# CurrMeas.net
KiCad netlist of a schematic drawn in EAGLE
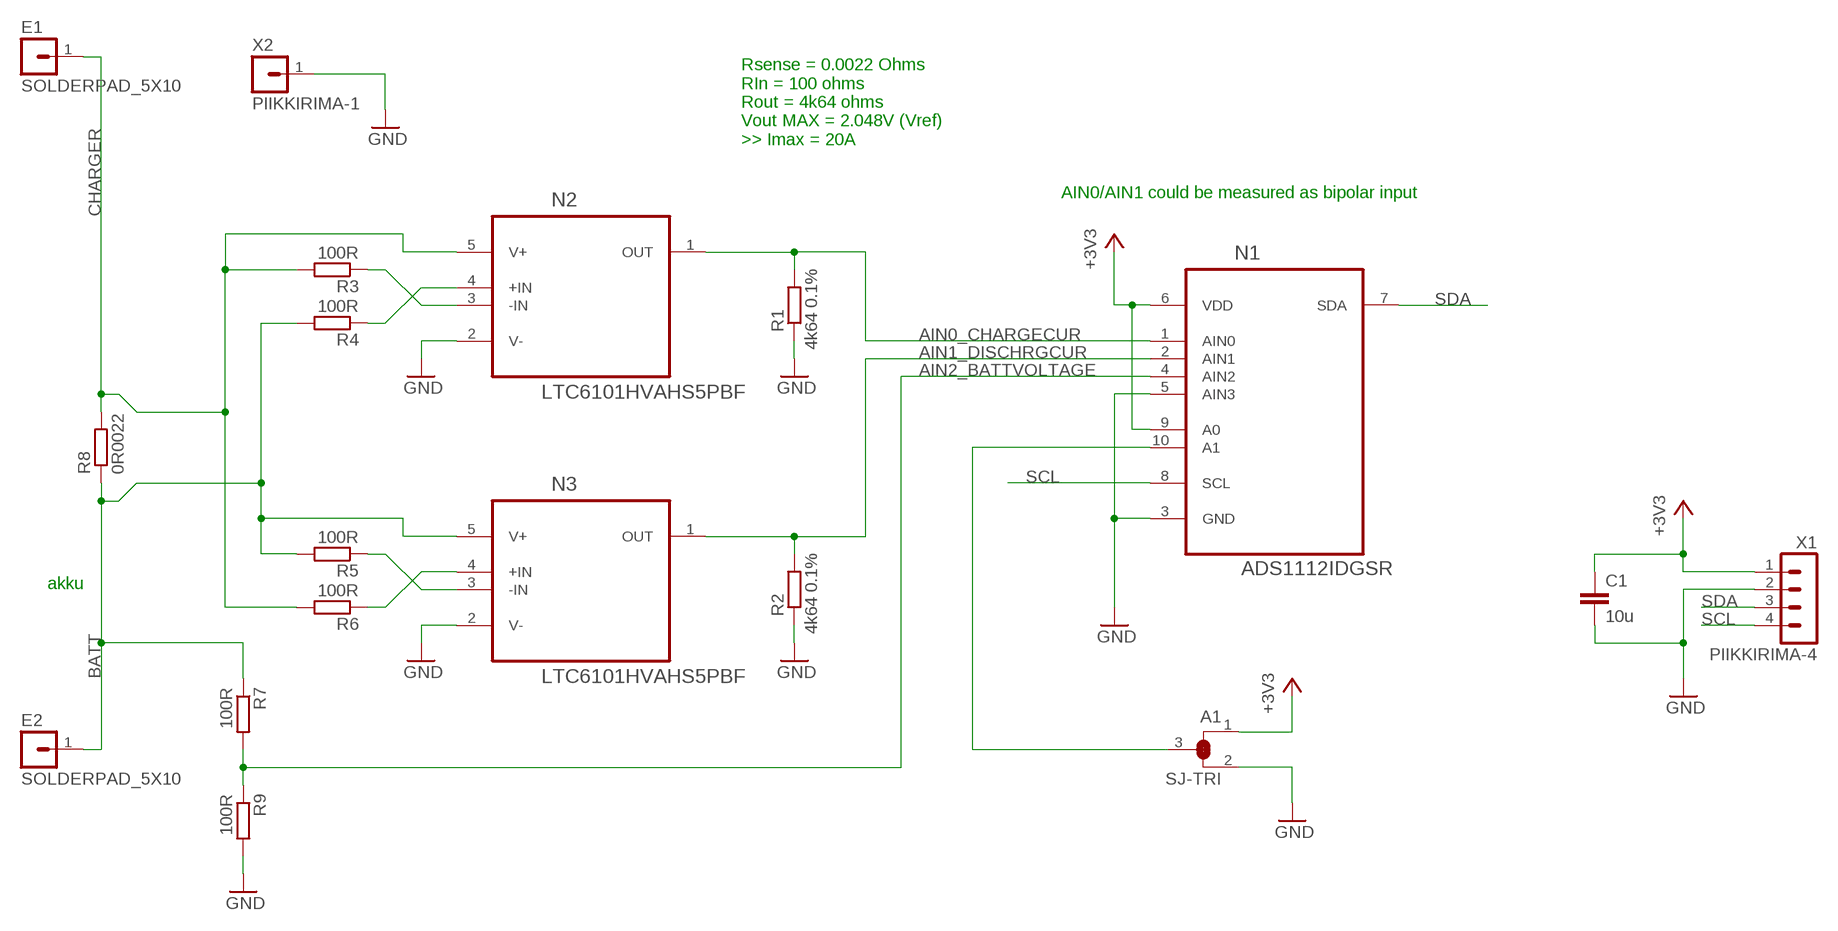
[diagram p0: schematic, sheet 1]

(export (version "E")
  (design (tool "Eeschema 10.0.6"))
  (components
    (comp (ref "A1")
      (value "SJ-TRI")
      (footprint "eagle-import:SJ-SMALL-TRI")
      (libsource (lib "eagle-import") (part "SJ-TRI"))
    )
    (comp (ref "C1")
      (value "10u")
      (footprint "eagle-import:C0805")
      (libsource (lib "eagle-import") (part "C-EUC0805"))
    )
    (comp (ref "E1")
      (value "SOLDERPAD_5X10")
      (footprint "eagle-import:SOLDERPAD_5X10")
      (libsource (lib "eagle-import") (part "SOLDERPAD_5X10"))
    )
    (comp (ref "E2")
      (value "SOLDERPAD_5X10")
      (footprint "eagle-import:SOLDERPAD_5X10")
      (libsource (lib "eagle-import") (part "SOLDERPAD_5X10"))
    )
    (comp (ref "N1")
      (value "ADS1112IDGSR")
      (footprint "eagle-import:SOP50P490X110-10N")
      (libsource (lib "eagle-import") (part "ADS1112IDGSR"))
    )
    (comp (ref "N2")
      (value "LTC6101HVAHS5PBF")
      (footprint "eagle-import:SOT95P280X100-5N")
      (fields (field (name "MPN") "LTC6101HVAHS5#PBF"))
      (libsource (lib "eagle-import") (part "LTC6101HVAHS5PBF"))
    )
    (comp (ref "N3")
      (value "LTC6101HVAHS5PBF")
      (footprint "eagle-import:SOT95P280X100-5N")
      (fields (field (name "MPN") "LTC6101HVAHS5#PBF"))
      (libsource (lib "eagle-import") (part "LTC6101HVAHS5PBF"))
    )
    (comp (ref "R1")
      (value "4k64 0.1%")
      (footprint "eagle-import:R0603")
      (libsource (lib "eagle-import") (part "R-EU_R0603"))
    )
    (comp (ref "R2")
      (value "4k64 0.1%")
      (footprint "eagle-import:R0603")
      (libsource (lib "eagle-import") (part "R-EU_R0603"))
    )
    (comp (ref "R3")
      (value "100R")
      (footprint "eagle-import:R0603")
      (libsource (lib "eagle-import") (part "R-EU_R0603"))
    )
    (comp (ref "R4")
      (value "100R")
      (footprint "eagle-import:R0603")
      (libsource (lib "eagle-import") (part "R-EU_R0603"))
    )
    (comp (ref "R5")
      (value "100R")
      (footprint "eagle-import:R0603")
      (libsource (lib "eagle-import") (part "R-EU_R0603"))
    )
    (comp (ref "R6")
      (value "100R")
      (footprint "eagle-import:R0603")
      (libsource (lib "eagle-import") (part "R-EU_R0603"))
    )
    (comp (ref "R7")
      (value "100R")
      (footprint "eagle-import:R0603")
      (libsource (lib "eagle-import") (part "R-EU_R0603"))
    )
    (comp (ref "R8")
      (value "0R0022")
      (footprint "eagle-import:R2512")
      (libsource (lib "eagle-import") (part "R-EU_R2512"))
    )
    (comp (ref "R9")
      (value "100R")
      (footprint "eagle-import:R0603")
      (libsource (lib "eagle-import") (part "R-EU_R0603"))
    )
    (comp (ref "X1")
      (value "PIIKKIRIMA-4")
      (footprint "eagle-import:PIIKKIRIMA-4")
      (libsource (lib "eagle-import") (part "PIIKKIRIMA-4"))
    )
    (comp (ref "X2")
      (value "PIIKKIRIMA-1")
      (footprint "eagle-import:PIIKKIRIMA-1")
      (libsource (lib "eagle-import") (part "PIIKKIRIMA-1"))
    )
  )
  (nets
    (net (code "1") (name "+3V3") (class "Default")
      (node (ref "A1") (pin "1") (pinfunction "1_1") (pintype "passive"))
      (node (ref "C1") (pin "1") (pinfunction "1_1") (pintype "passive"))
      (node (ref "N1") (pin "6") (pinfunction "VDD_6") (pintype "power_in"))
      (node (ref "N1") (pin "9") (pinfunction "A0_9") (pintype "input"))
      (node (ref "X1") (pin "1") (pinfunction "1_1") (pintype "passive"))
    )
    (net (code "2") (name "/AIN0_CHARGECUR") (class "Default")
      (node (ref "N1") (pin "1") (pinfunction "AIN0_1") (pintype "input"))
      (node (ref "N2") (pin "1") (pinfunction "OUT_1") (pintype "output"))
      (node (ref "R1") (pin "2") (pinfunction "2_2") (pintype "passive"))
    )
    (net (code "3") (name "/AIN1_DISCHRGCUR") (class "Default")
      (node (ref "N1") (pin "2") (pinfunction "AIN1_2") (pintype "input"))
      (node (ref "N3") (pin "1") (pinfunction "OUT_1") (pintype "output"))
      (node (ref "R2") (pin "2") (pinfunction "2_2") (pintype "passive"))
    )
    (net (code "4") (name "/AIN2_BATTVOLTAGE") (class "Default")
      (node (ref "N1") (pin "4") (pinfunction "AIN2_4") (pintype "input"))
      (node (ref "R7") (pin "2") (pinfunction "2_2") (pintype "passive"))
      (node (ref "R9") (pin "1") (pinfunction "1_1") (pintype "passive"))
    )
    (net (code "5") (name "/BATT") (class "Default")
      (node (ref "E2") (pin "1") (pinfunction "1_1") (pintype "passive"))
      (node (ref "N3") (pin "5") (pinfunction "V+_5") (pintype "power_in"))
      (node (ref "R4") (pin "2") (pinfunction "2_2") (pintype "passive"))
      (node (ref "R5") (pin "2") (pinfunction "2_2") (pintype "passive"))
      (node (ref "R7") (pin "1") (pinfunction "1_1") (pintype "passive"))
      (node (ref "R8") (pin "1") (pinfunction "1_1") (pintype "passive"))
    )
    (net (code "6") (name "/CHARGER") (class "Default")
      (node (ref "E1") (pin "1") (pinfunction "1_1") (pintype "passive"))
      (node (ref "N2") (pin "5") (pinfunction "V+_5") (pintype "power_in"))
      (node (ref "R3") (pin "2") (pinfunction "2_2") (pintype "passive"))
      (node (ref "R6") (pin "2") (pinfunction "2_2") (pintype "passive"))
      (node (ref "R8") (pin "2") (pinfunction "2_2") (pintype "passive"))
    )
    (net (code "7") (name "/SCL") (class "Default")
      (node (ref "N1") (pin "8") (pinfunction "SCL_8") (pintype "input"))
      (node (ref "X1") (pin "4") (pinfunction "4_4") (pintype "passive"))
    )
    (net (code "8") (name "/SDA") (class "Default")
      (node (ref "N1") (pin "7") (pinfunction "SDA_7") (pintype "bidirectional"))
      (node (ref "X1") (pin "3") (pinfunction "3_3") (pintype "passive"))
    )
    (net (code "9") (name "GND") (class "Default")
      (node (ref "A1") (pin "2") (pinfunction "2_2") (pintype "passive"))
      (node (ref "C1") (pin "2") (pinfunction "2_2") (pintype "passive"))
      (node (ref "N1") (pin "3") (pinfunction "GND_3") (pintype "passive"))
      (node (ref "N1") (pin "5") (pinfunction "AIN3_5") (pintype "input"))
      (node (ref "N2") (pin "2") (pinfunction "V-_2") (pintype "power_in"))
      (node (ref "N3") (pin "2") (pinfunction "V-_2") (pintype "power_in"))
      (node (ref "R1") (pin "1") (pinfunction "1_1") (pintype "passive"))
      (node (ref "R2") (pin "1") (pinfunction "1_1") (pintype "passive"))
      (node (ref "R9") (pin "2") (pinfunction "2_2") (pintype "passive"))
      (node (ref "X1") (pin "2") (pinfunction "2_2") (pintype "passive"))
      (node (ref "X2") (pin "1") (pinfunction "1_1") (pintype "passive"))
    )
    (net (code "10") (name "Net-(N1-A1)") (class "Default")
      (node (ref "A1") (pin "3") (pinfunction "3_3") (pintype "passive"))
      (node (ref "N1") (pin "10") (pinfunction "A1_10") (pintype "input"))
    )
    (net (code "11") (name "Net-(N2-+IN)") (class "Default")
      (node (ref "N2") (pin "4") (pinfunction "+IN_4") (pintype "input"))
      (node (ref "R4") (pin "1") (pinfunction "1_1") (pintype "passive"))
    )
    (net (code "12") (name "Net-(N2--IN)") (class "Default")
      (node (ref "N2") (pin "3") (pinfunction "-IN_3") (pintype "input"))
      (node (ref "R3") (pin "1") (pinfunction "1_1") (pintype "passive"))
    )
    (net (code "13") (name "Net-(N3-+IN)") (class "Default")
      (node (ref "N3") (pin "4") (pinfunction "+IN_4") (pintype "input"))
      (node (ref "R6") (pin "1") (pinfunction "1_1") (pintype "passive"))
    )
    (net (code "14") (name "Net-(N3--IN)") (class "Default")
      (node (ref "N3") (pin "3") (pinfunction "-IN_3") (pintype "input"))
      (node (ref "R5") (pin "1") (pinfunction "1_1") (pintype "passive"))
    )
  )
)
